# shift_register-control.net
KiCad netlist of a schematic drawn in EAGLE
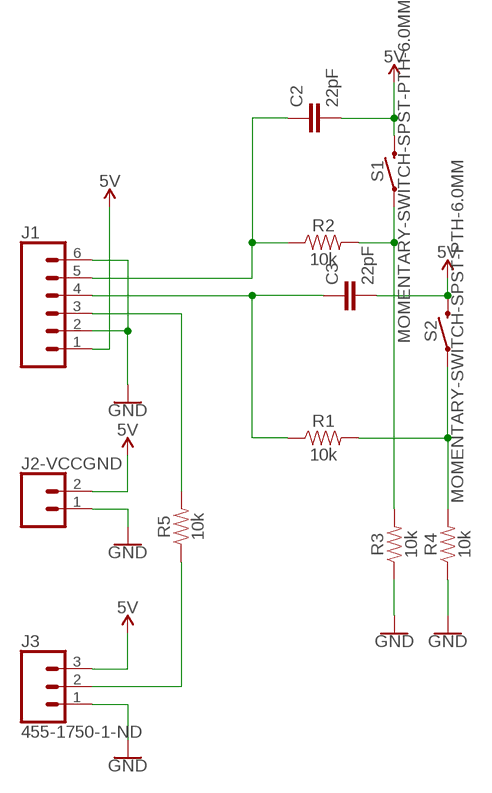
[diagram p0: schematic, sheet 1]

(export (version "E")
  (design (tool "Eeschema 10.0.6"))
  (components
    (comp (ref "C2")
      (value "22pF")
      (footprint "eagle-import:CAP-PTH-2.54")
      (libsource (lib "eagle-import") (part "22PF-PTH-2.54MM-200V-5%"))
    )
    (comp (ref "C3")
      (value "22pF")
      (footprint "eagle-import:CAP-PTH-2.54")
      (libsource (lib "eagle-import") (part "22PF-PTH-2.54MM-200V-5%"))
    )
    (comp (ref "J1")
      (value "CONN_06SILK_FEMALE_PTH")
      (footprint "eagle-import:1X06")
      (libsource (lib "eagle-import") (part "CONN_06SILK_FEMALE_PTH"))
    )
    (comp (ref "J2-VCCGND")
      (value "CONN_02")
      (footprint "eagle-import:1X02")
      (libsource (lib "eagle-import") (part "CONN_02"))
    )
    (comp (ref "J3")
      (value "455-1750-1-ND")
      (footprint "eagle-import:1X03")
      (libsource (lib "eagle-import") (part "CONN_03"))
    )
    (comp (ref "R1")
      (value "10k")
      (footprint "eagle-import:AXIAL-0.3")
      (libsource (lib "eagle-import") (part "10KOHM-HORIZ-1/4W-5%"))
    )
    (comp (ref "R2")
      (value "10k")
      (footprint "eagle-import:AXIAL-0.3")
      (libsource (lib "eagle-import") (part "10KOHM-HORIZ-1/4W-5%"))
    )
    (comp (ref "R3")
      (value "10k")
      (footprint "eagle-import:AXIAL-0.3")
      (libsource (lib "eagle-import") (part "10KOHM-HORIZ-1/4W-5%"))
    )
    (comp (ref "R4")
      (value "10k")
      (footprint "eagle-import:AXIAL-0.3")
      (libsource (lib "eagle-import") (part "10KOHM-HORIZ-1/4W-5%"))
    )
    (comp (ref "R5")
      (value "10k")
      (footprint "eagle-import:AXIAL-0.3")
      (libsource (lib "eagle-import") (part "10KOHM-HORIZ-1/4W-5%"))
    )
    (comp (ref "S1")
      (value "MOMENTARY-SWITCH-SPST-PTH-6.0MM")
      (footprint "eagle-import:TACTILE_SWITCH_PTH_6.0MM")
      (libsource (lib "eagle-import") (part "MOMENTARY-SWITCH-SPST-PTH-6.0MM"))
    )
    (comp (ref "S2")
      (value "MOMENTARY-SWITCH-SPST-PTH-6.0MM")
      (footprint "eagle-import:TACTILE_SWITCH_PTH_6.0MM")
      (libsource (lib "eagle-import") (part "MOMENTARY-SWITCH-SPST-PTH-6.0MM"))
    )
  )
  (nets
    (net (code "1") (name "5V") (class "Default")
      (node (ref "C2") (pin "2") (pinfunction "2_2") (pintype "passive"))
      (node (ref "C3") (pin "2") (pinfunction "2_2") (pintype "passive"))
      (node (ref "J1") (pin "1") (pinfunction "1_1") (pintype "passive"))
      (node (ref "J2-VCCGND") (pin "2") (pinfunction "2_2") (pintype "passive"))
      (node (ref "J3") (pin "3") (pinfunction "3_3") (pintype "passive"))
      (node (ref "S1") (pin "3") (pinfunction "2_3") (pintype "passive"))
      (node (ref "S2") (pin "3") (pinfunction "2_3") (pintype "passive"))
    )
    (net (code "2") (name "GND") (class "Default")
      (node (ref "J1") (pin "2") (pinfunction "2_2") (pintype "passive"))
      (node (ref "J1") (pin "6") (pinfunction "6_6") (pintype "passive"))
      (node (ref "J2-VCCGND") (pin "1") (pinfunction "1_1") (pintype "passive"))
      (node (ref "J3") (pin "1") (pinfunction "1_1") (pintype "passive"))
      (node (ref "R3") (pin "P$1") (pinfunction "1_P$1") (pintype "passive"))
      (node (ref "R4") (pin "P$1") (pinfunction "1_P$1") (pintype "passive"))
    )
    (net (code "3") (name "Net-(R1-1)") (class "Default")
      (node (ref "C3") (pin "1") (pinfunction "1_1") (pintype "passive"))
      (node (ref "J1") (pin "4") (pinfunction "4_4") (pintype "passive"))
      (node (ref "R1") (pin "P$1") (pinfunction "1_P$1") (pintype "passive"))
    )
    (net (code "4") (name "Net-(R1-2)") (class "Default")
      (node (ref "R1") (pin "P$2") (pinfunction "2_P$2") (pintype "passive"))
      (node (ref "R4") (pin "P$2") (pinfunction "2_P$2") (pintype "passive"))
      (node (ref "S2") (pin "1") (pinfunction "1_1") (pintype "passive"))
    )
    (net (code "5") (name "Net-(R2-1)") (class "Default")
      (node (ref "C2") (pin "1") (pinfunction "1_1") (pintype "passive"))
      (node (ref "J1") (pin "5") (pinfunction "5_5") (pintype "passive"))
      (node (ref "R2") (pin "P$1") (pinfunction "1_P$1") (pintype "passive"))
    )
    (net (code "6") (name "Net-(R2-2)") (class "Default")
      (node (ref "R2") (pin "P$2") (pinfunction "2_P$2") (pintype "passive"))
      (node (ref "R3") (pin "P$2") (pinfunction "2_P$2") (pintype "passive"))
      (node (ref "S1") (pin "1") (pinfunction "1_1") (pintype "passive"))
    )
    (net (code "7") (name "Net-(R5-1)") (class "Default")
      (node (ref "J3") (pin "2") (pinfunction "2_2") (pintype "passive"))
      (node (ref "R5") (pin "P$1") (pinfunction "1_P$1") (pintype "passive"))
    )
    (net (code "8") (name "Net-(R5-2)") (class "Default")
      (node (ref "J1") (pin "3") (pinfunction "3_3") (pintype "passive"))
      (node (ref "R5") (pin "P$2") (pinfunction "2_P$2") (pintype "passive"))
    )
  )
)
